# SatBusConnections.net
KiCad netlist of a schematic drawn in Altium Designer
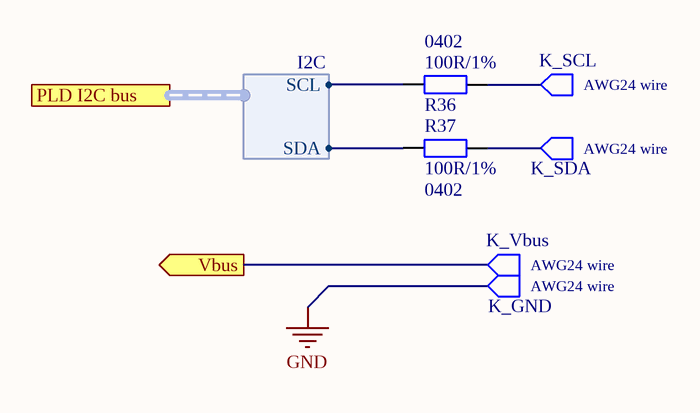
[diagram p0: SatBusConnections.SchDoc]

(export (version "E")
  (design (tool "Eeschema 10.0.6"))
  (components
    (comp (ref "K_GND")
      (value "AWG24 wire")
      (footprint "wire-awg26-1_stress-relief")
      (description "Single wire AWG26 solder point.")
      (libsource (lib "connectors_printed-circuit-board") (part "wire-awg26-1"))
    )
    (comp (ref "K_SCL")
      (value "AWG24 wire")
      (footprint "wire-awg26-1_stress-relief")
      (description "Single wire AWG26 solder point.")
      (libsource (lib "connectors_printed-circuit-board") (part "wire-awg26-1"))
    )
    (comp (ref "K_SDA")
      (value "AWG24 wire")
      (footprint "wire-awg26-1_stress-relief")
      (description "Single wire AWG26 solder point.")
      (libsource (lib "connectors_printed-circuit-board") (part "wire-awg26-1"))
    )
    (comp (ref "K_Vbus")
      (value "AWG24 wire")
      (footprint "wire-awg26-1_stress-relief")
      (description "Single wire AWG26 solder point.")
      (libsource (lib "connectors_printed-circuit-board") (part "wire-awg26-1"))
    )
    (comp (ref "R36")
      (value "100R/1%")
      (footprint "SMD_Resistor_0402")
      (description "100R/1% Vishay CRCW 0402 Resistor. 63mW, 100ppm, 50V.")
      (fields
        (field (name "MANUFACTURER") "Vishay")
        (field (name "MANUFACTURERPARTNUMBER") "CRCW0402100RFKxxxx")
        (field (name "PACKAGE") "0402")
      )
      (libsource (lib "resistors") (part "CRCW0402100RFKxxxx"))
    )
    (comp (ref "R37")
      (value "100R/1%")
      (footprint "SMD_Resistor_0402")
      (description "100R/1% Vishay CRCW 0402 Resistor. 63mW, 100ppm, 50V.")
      (fields
        (field (name "MANUFACTURER") "Vishay")
        (field (name "MANUFACTURERPARTNUMBER") "CRCW0402100RFKxxxx")
        (field (name "PACKAGE") "0402")
      )
      (libsource (lib "resistors") (part "CRCW0402100RFKxxxx"))
    )
  )
  (nets
    (net (code "2") (name "/SCL") (class "Default")
      (node (ref "R36") (pin "1") (pinfunction "1_1") (pintype "passive"))
    )
    (net (code "3") (name "/SDA") (class "Default")
      (node (ref "R37") (pin "1") (pinfunction "1_1") (pintype "passive"))
    )
    (net (code "4") (name "/Vbus") (class "Default")
      (node (ref "K_Vbus") (pin "1") (pinfunction "1_1") (pintype "passive"))
    )
    (net (code "6") (name "GND") (class "Default")
      (node (ref "K_GND") (pin "1") (pinfunction "1_1") (pintype "passive"))
    )
    (net (code "7") (name "Net-(K_SCL-Pad1)") (class "Default")
      (node (ref "K_SCL") (pin "1") (pinfunction "1_1") (pintype "passive"))
      (node (ref "R36") (pin "2") (pinfunction "2_2") (pintype "passive"))
    )
    (net (code "8") (name "Net-(K_SDA-Pad1)") (class "Default")
      (node (ref "K_SDA") (pin "1") (pinfunction "1_1") (pintype "passive"))
      (node (ref "R37") (pin "2") (pinfunction "2_2") (pintype "passive"))
    )
  )
)
